# gameboy_esp_osc.net
KiCad netlist of a schematic drawn in EAGLE
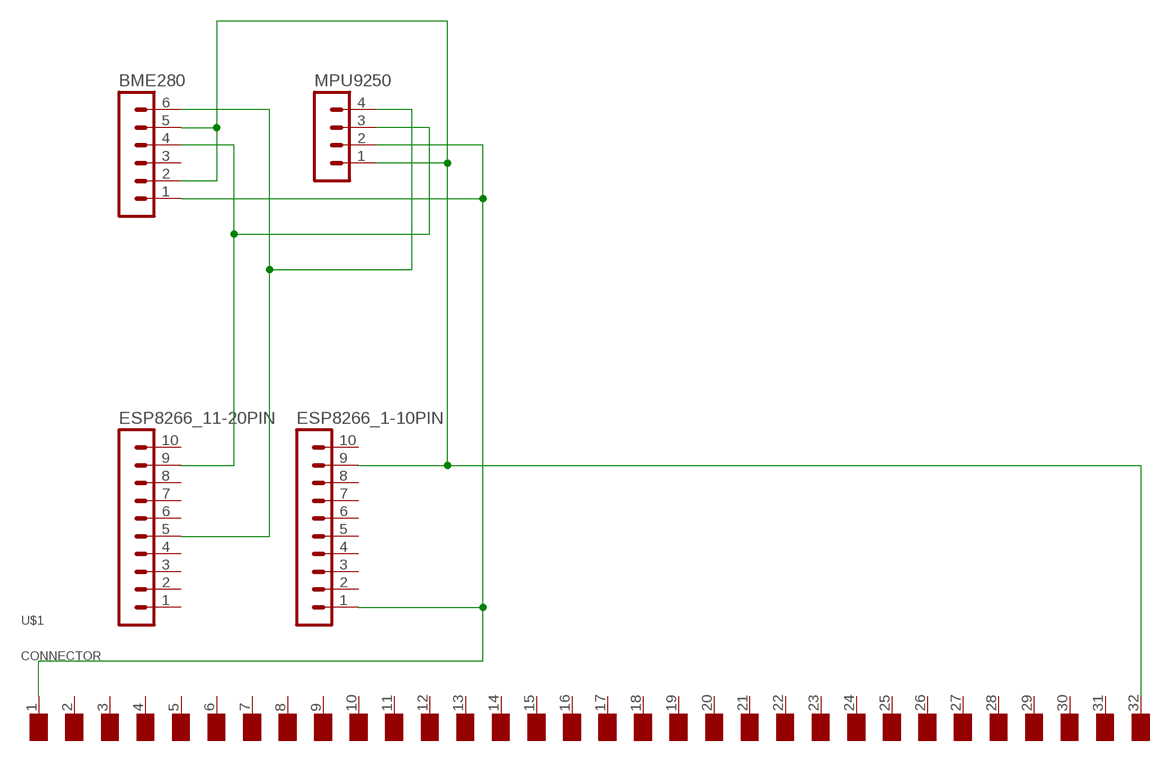
[diagram p0: schematic, sheet 1]

(export (version "E")
  (design (tool "Eeschema 10.0.6"))
  (components
    (comp (ref "BME280")
      (value "MA06-1")
      (footprint "eagle-import:MA06-1")
      (libsource (lib "eagle-import") (part "MA06-1"))
    )
    (comp (ref "ESP8266_1-10PIN")
      (value "MA10-1")
      (footprint "eagle-import:MA10-1")
      (libsource (lib "eagle-import") (part "MA10-1"))
    )
    (comp (ref "ESP8266_11-20PIN")
      (value "MA10-1")
      (footprint "eagle-import:MA10-1")
      (libsource (lib "eagle-import") (part "MA10-1"))
    )
    (comp (ref "MPU9250")
      (value "MA04-1")
      (footprint "eagle-import:MA04-1")
      (libsource (lib "eagle-import") (part "MA04-1"))
    )
    (comp (ref "U$1")
      (value "CONNECTOR")
      (footprint "eagle-import:CONNECTOR")
      (libsource (lib "eagle-import") (part "CONNECTOR"))
    )
  )
  (nets
    (net (code "1") (name "Net-(BME280-Pad4)") (class "Default")
      (node (ref "BME280") (pin "4") (pinfunction "4_4") (pintype "passive"))
      (node (ref "ESP8266_11-20PIN") (pin "9") (pinfunction "9_9") (pintype "passive"))
      (node (ref "MPU9250") (pin "3") (pinfunction "3_3") (pintype "passive"))
    )
    (net (code "2") (name "Net-(BME280-Pad6)") (class "Default")
      (node (ref "BME280") (pin "6") (pinfunction "6_6") (pintype "passive"))
      (node (ref "ESP8266_11-20PIN") (pin "5") (pinfunction "5_5") (pintype "passive"))
      (node (ref "MPU9250") (pin "4") (pinfunction "4_4") (pintype "passive"))
    )
    (net (code "3") (name "Net-(U$1-GND)") (class "Default")
      (node (ref "BME280") (pin "2") (pinfunction "2_2") (pintype "passive"))
      (node (ref "BME280") (pin "5") (pinfunction "5_5") (pintype "passive"))
      (node (ref "ESP8266_1-10PIN") (pin "9") (pinfunction "9_9") (pintype "passive"))
      (node (ref "MPU9250") (pin "1") (pinfunction "1_1") (pintype "passive"))
      (node (ref "U$1") (pin "32") (pinfunction "GND_32") (pintype "power_in"))
    )
    (net (code "4") (name "Net-(U$1-VDD)") (class "Default")
      (node (ref "BME280") (pin "1") (pinfunction "1_1") (pintype "passive"))
      (node (ref "ESP8266_1-10PIN") (pin "1") (pinfunction "1_1") (pintype "passive"))
      (node (ref "MPU9250") (pin "2") (pinfunction "2_2") (pintype "passive"))
      (node (ref "U$1") (pin "1") (pinfunction "VDD_1") (pintype "power_in"))
    )
    (net (code "5") (name "unconnected-(BME280-Pad3)") (class "Default")
      (node (ref "BME280") (pin "3") (pinfunction "3_3") (pintype "passive"))
    )
    (net (code "6") (name "unconnected-(ESP8266_1-10PIN-Pad2)") (class "Default")
      (node (ref "ESP8266_1-10PIN") (pin "2") (pinfunction "2_2") (pintype "passive"))
    )
    (net (code "7") (name "unconnected-(ESP8266_1-10PIN-Pad3)") (class "Default")
      (node (ref "ESP8266_1-10PIN") (pin "3") (pinfunction "3_3") (pintype "passive"))
    )
    (net (code "8") (name "unconnected-(ESP8266_1-10PIN-Pad4)") (class "Default")
      (node (ref "ESP8266_1-10PIN") (pin "4") (pinfunction "4_4") (pintype "passive"))
    )
    (net (code "9") (name "unconnected-(ESP8266_1-10PIN-Pad5)") (class "Default")
      (node (ref "ESP8266_1-10PIN") (pin "5") (pinfunction "5_5") (pintype "passive"))
    )
    (net (code "10") (name "unconnected-(ESP8266_1-10PIN-Pad6)") (class "Default")
      (node (ref "ESP8266_1-10PIN") (pin "6") (pinfunction "6_6") (pintype "passive"))
    )
    (net (code "11") (name "unconnected-(ESP8266_1-10PIN-Pad7)") (class "Default")
      (node (ref "ESP8266_1-10PIN") (pin "7") (pinfunction "7_7") (pintype "passive"))
    )
    (net (code "12") (name "unconnected-(ESP8266_1-10PIN-Pad8)") (class "Default")
      (node (ref "ESP8266_1-10PIN") (pin "8") (pinfunction "8_8") (pintype "passive"))
    )
    (net (code "13") (name "unconnected-(ESP8266_1-10PIN-Pad10)") (class "Default")
      (node (ref "ESP8266_1-10PIN") (pin "10") (pinfunction "10_10") (pintype "passive"))
    )
    (net (code "14") (name "unconnected-(ESP8266_11-20PIN-Pad1)") (class "Default")
      (node (ref "ESP8266_11-20PIN") (pin "1") (pinfunction "1_1") (pintype "passive"))
    )
    (net (code "15") (name "unconnected-(ESP8266_11-20PIN-Pad2)") (class "Default")
      (node (ref "ESP8266_11-20PIN") (pin "2") (pinfunction "2_2") (pintype "passive"))
    )
    (net (code "16") (name "unconnected-(ESP8266_11-20PIN-Pad3)") (class "Default")
      (node (ref "ESP8266_11-20PIN") (pin "3") (pinfunction "3_3") (pintype "passive"))
    )
    (net (code "17") (name "unconnected-(ESP8266_11-20PIN-Pad4)") (class "Default")
      (node (ref "ESP8266_11-20PIN") (pin "4") (pinfunction "4_4") (pintype "passive"))
    )
    (net (code "18") (name "unconnected-(ESP8266_11-20PIN-Pad6)") (class "Default")
      (node (ref "ESP8266_11-20PIN") (pin "6") (pinfunction "6_6") (pintype "passive"))
    )
    (net (code "19") (name "unconnected-(ESP8266_11-20PIN-Pad7)") (class "Default")
      (node (ref "ESP8266_11-20PIN") (pin "7") (pinfunction "7_7") (pintype "passive"))
    )
    (net (code "20") (name "unconnected-(ESP8266_11-20PIN-Pad8)") (class "Default")
      (node (ref "ESP8266_11-20PIN") (pin "8") (pinfunction "8_8") (pintype "passive"))
    )
    (net (code "21") (name "unconnected-(ESP8266_11-20PIN-Pad10)") (class "Default")
      (node (ref "ESP8266_11-20PIN") (pin "10") (pinfunction "10_10") (pintype "passive"))
    )
    (net (code "22") (name "unconnected-(U$1-A0-Pad6)") (class "Default")
      (node (ref "U$1") (pin "6") (pinfunction "A0_6") (pintype "bidirectional"))
    )
    (net (code "23") (name "unconnected-(U$1-A1-Pad7)") (class "Default")
      (node (ref "U$1") (pin "7") (pinfunction "A1_7") (pintype "bidirectional"))
    )
    (net (code "24") (name "unconnected-(U$1-A2-Pad8)") (class "Default")
      (node (ref "U$1") (pin "8") (pinfunction "A2_8") (pintype "bidirectional"))
    )
    (net (code "25") (name "unconnected-(U$1-A3-Pad9)") (class "Default")
      (node (ref "U$1") (pin "9") (pinfunction "A3_9") (pintype "bidirectional"))
    )
    (net (code "26") (name "unconnected-(U$1-A4-Pad10)") (class "Default")
      (node (ref "U$1") (pin "10") (pinfunction "A4_10") (pintype "bidirectional"))
    )
    (net (code "27") (name "unconnected-(U$1-A5-Pad11)") (class "Default")
      (node (ref "U$1") (pin "11") (pinfunction "A5_11") (pintype "bidirectional"))
    )
    (net (code "28") (name "unconnected-(U$1-A6-Pad12)") (class "Default")
      (node (ref "U$1") (pin "12") (pinfunction "A6_12") (pintype "bidirectional"))
    )
    (net (code "29") (name "unconnected-(U$1-A7-Pad13)") (class "Default")
      (node (ref "U$1") (pin "13") (pinfunction "A7_13") (pintype "bidirectional"))
    )
    (net (code "30") (name "unconnected-(U$1-A8-Pad14)") (class "Default")
      (node (ref "U$1") (pin "14") (pinfunction "A8_14") (pintype "bidirectional"))
    )
    (net (code "31") (name "unconnected-(U$1-A9-Pad15)") (class "Default")
      (node (ref "U$1") (pin "15") (pinfunction "A9_15") (pintype "bidirectional"))
    )
    (net (code "32") (name "unconnected-(U$1-A10-Pad16)") (class "Default")
      (node (ref "U$1") (pin "16") (pinfunction "A10_16") (pintype "bidirectional"))
    )
    (net (code "33") (name "unconnected-(U$1-A11-Pad17)") (class "Default")
      (node (ref "U$1") (pin "17") (pinfunction "A11_17") (pintype "bidirectional"))
    )
    (net (code "34") (name "unconnected-(U$1-A12-Pad18)") (class "Default")
      (node (ref "U$1") (pin "18") (pinfunction "A12_18") (pintype "bidirectional"))
    )
    (net (code "35") (name "unconnected-(U$1-A13-Pad19)") (class "Default")
      (node (ref "U$1") (pin "19") (pinfunction "A13_19") (pintype "bidirectional"))
    )
    (net (code "36") (name "unconnected-(U$1-A14-Pad20)") (class "Default")
      (node (ref "U$1") (pin "20") (pinfunction "A14_20") (pintype "bidirectional"))
    )
    (net (code "37") (name "unconnected-(U$1-A15-Pad21)") (class "Default")
      (node (ref "U$1") (pin "21") (pinfunction "A15_21") (pintype "bidirectional"))
    )
    (net (code "38") (name "unconnected-(U$1-D0-Pad22)") (class "Default")
      (node (ref "U$1") (pin "22") (pinfunction "D0_22") (pintype "bidirectional"))
    )
    (net (code "39") (name "unconnected-(U$1-D1-Pad23)") (class "Default")
      (node (ref "U$1") (pin "23") (pinfunction "D1_23") (pintype "bidirectional"))
    )
    (net (code "40") (name "unconnected-(U$1-D2-Pad24)") (class "Default")
      (node (ref "U$1") (pin "24") (pinfunction "D2_24") (pintype "bidirectional"))
    )
    (net (code "41") (name "unconnected-(U$1-D3-Pad25)") (class "Default")
      (node (ref "U$1") (pin "25") (pinfunction "D3_25") (pintype "bidirectional"))
    )
    (net (code "42") (name "unconnected-(U$1-D4-Pad26)") (class "Default")
      (node (ref "U$1") (pin "26") (pinfunction "D4_26") (pintype "bidirectional"))
    )
    (net (code "43") (name "unconnected-(U$1-D5-Pad27)") (class "Default")
      (node (ref "U$1") (pin "27") (pinfunction "D5_27") (pintype "bidirectional"))
    )
    (net (code "44") (name "unconnected-(U$1-D6-Pad28)") (class "Default")
      (node (ref "U$1") (pin "28") (pinfunction "D6_28") (pintype "bidirectional"))
    )
    (net (code "45") (name "unconnected-(U$1-D7-Pad29)") (class "Default")
      (node (ref "U$1") (pin "29") (pinfunction "D7_29") (pintype "bidirectional"))
    )
    (net (code "46") (name "unconnected-(U$1-NC-Pad2)") (class "Default")
      (node (ref "U$1") (pin "2") (pinfunction "NC_2") (pintype "no_connect"))
    )
    (net (code "47") (name "unconnected-(U$1-VIN-Pad31)") (class "Default")
      (node (ref "U$1") (pin "31") (pinfunction "VIN_31") (pintype "bidirectional"))
    )
    (net (code "48") (name "unconnected-(U$1-{slash}RCS-Pad5)") (class "Default")
      (node (ref "U$1") (pin "5") (pinfunction "/RCS_5") (pintype "bidirectional"))
    )
    (net (code "49") (name "unconnected-(U$1-{slash}RD-Pad4)") (class "Default")
      (node (ref "U$1") (pin "4") (pinfunction "/RD_4") (pintype "bidirectional"))
    )
    (net (code "50") (name "unconnected-(U$1-{slash}RS-Pad30)") (class "Default")
      (node (ref "U$1") (pin "30") (pinfunction "/RS_30") (pintype "bidirectional"))
    )
    (net (code "51") (name "unconnected-(U$1-{slash}WR-Pad3)") (class "Default")
      (node (ref "U$1") (pin "3") (pinfunction "/WR_3") (pintype "bidirectional"))
    )
  )
)
